# opencanusb2.net
KiCad netlist of a schematic drawn in EAGLE
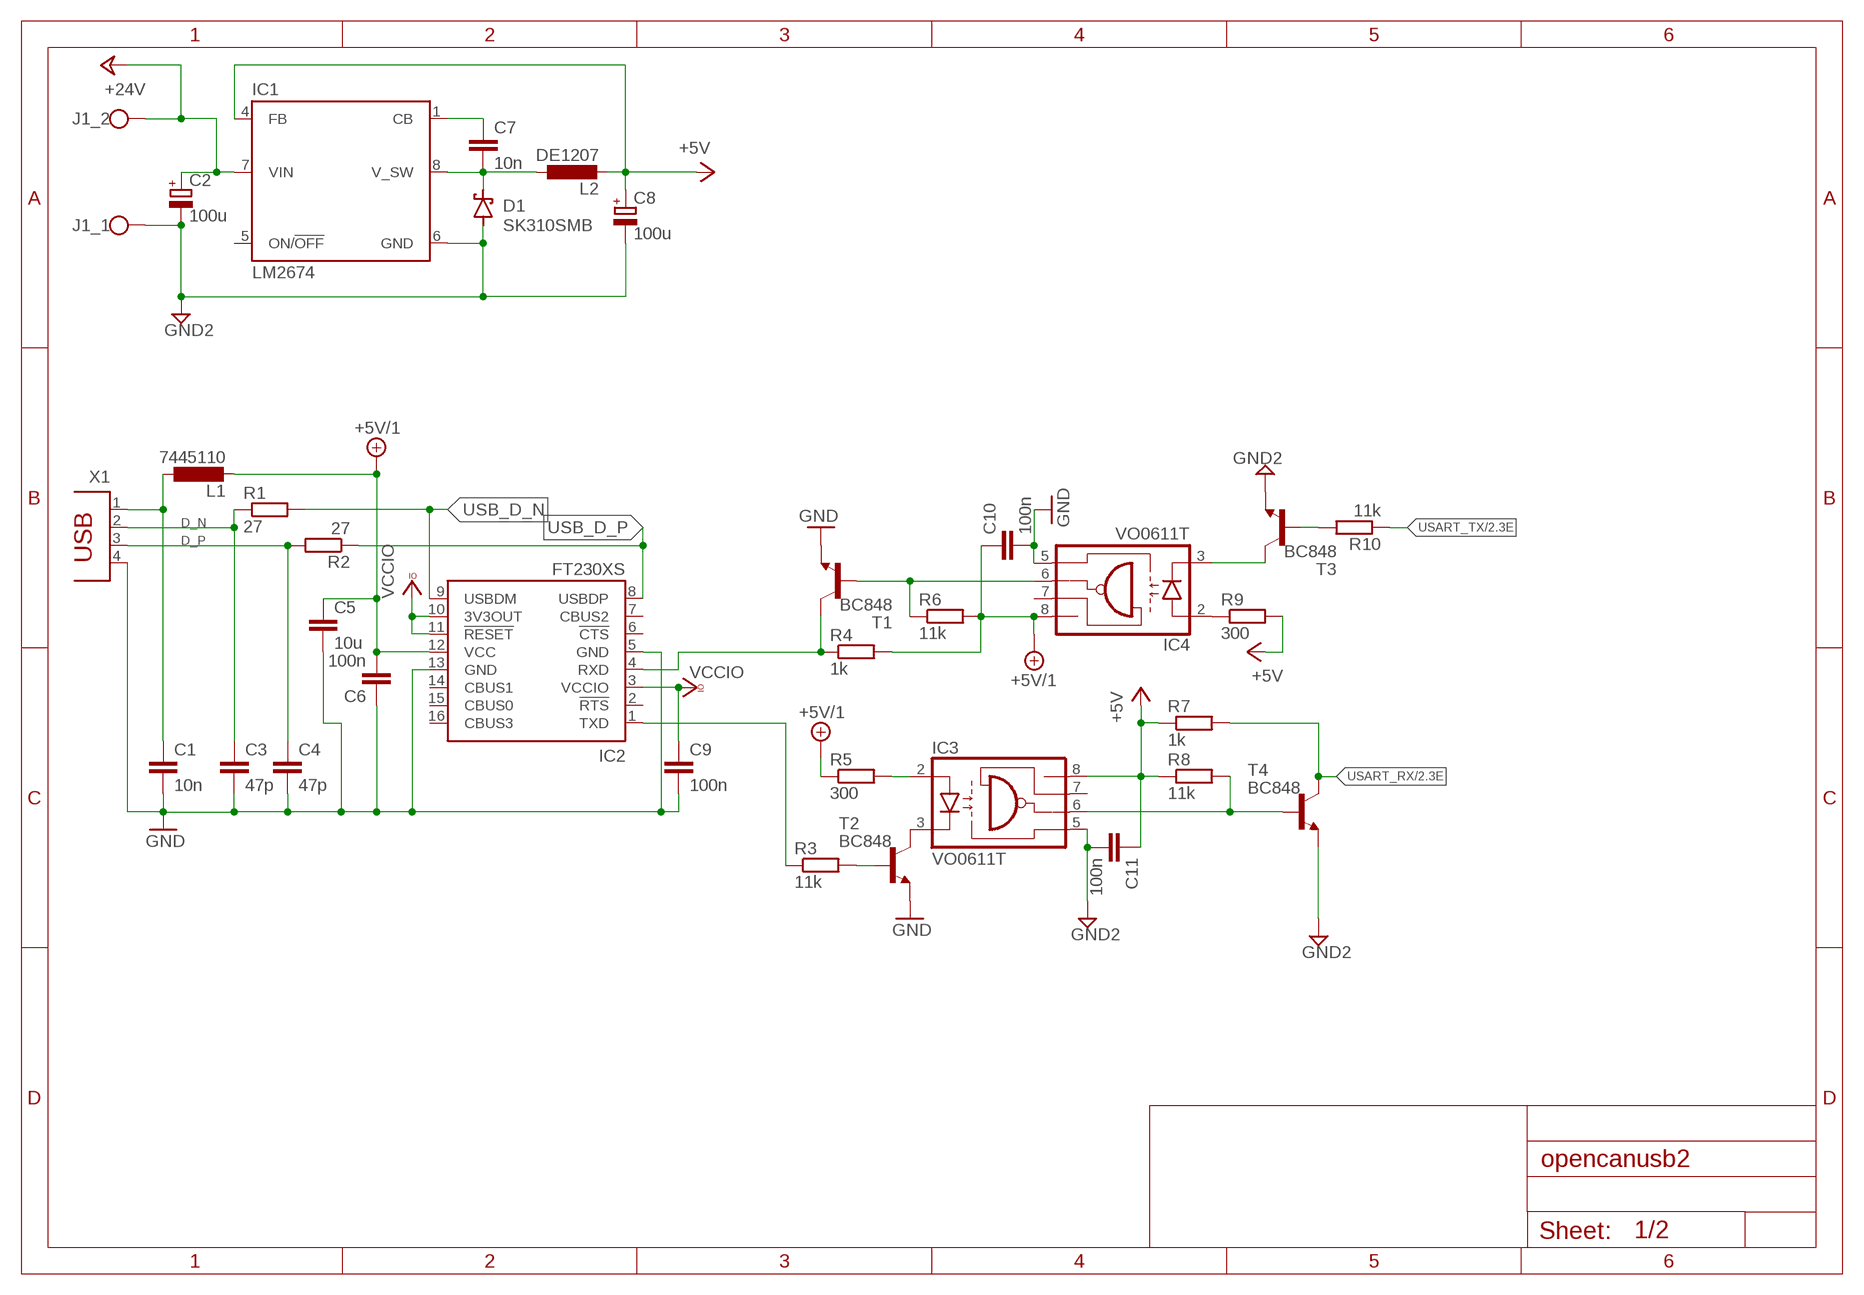
[diagram p0: schematic, sheet 1]
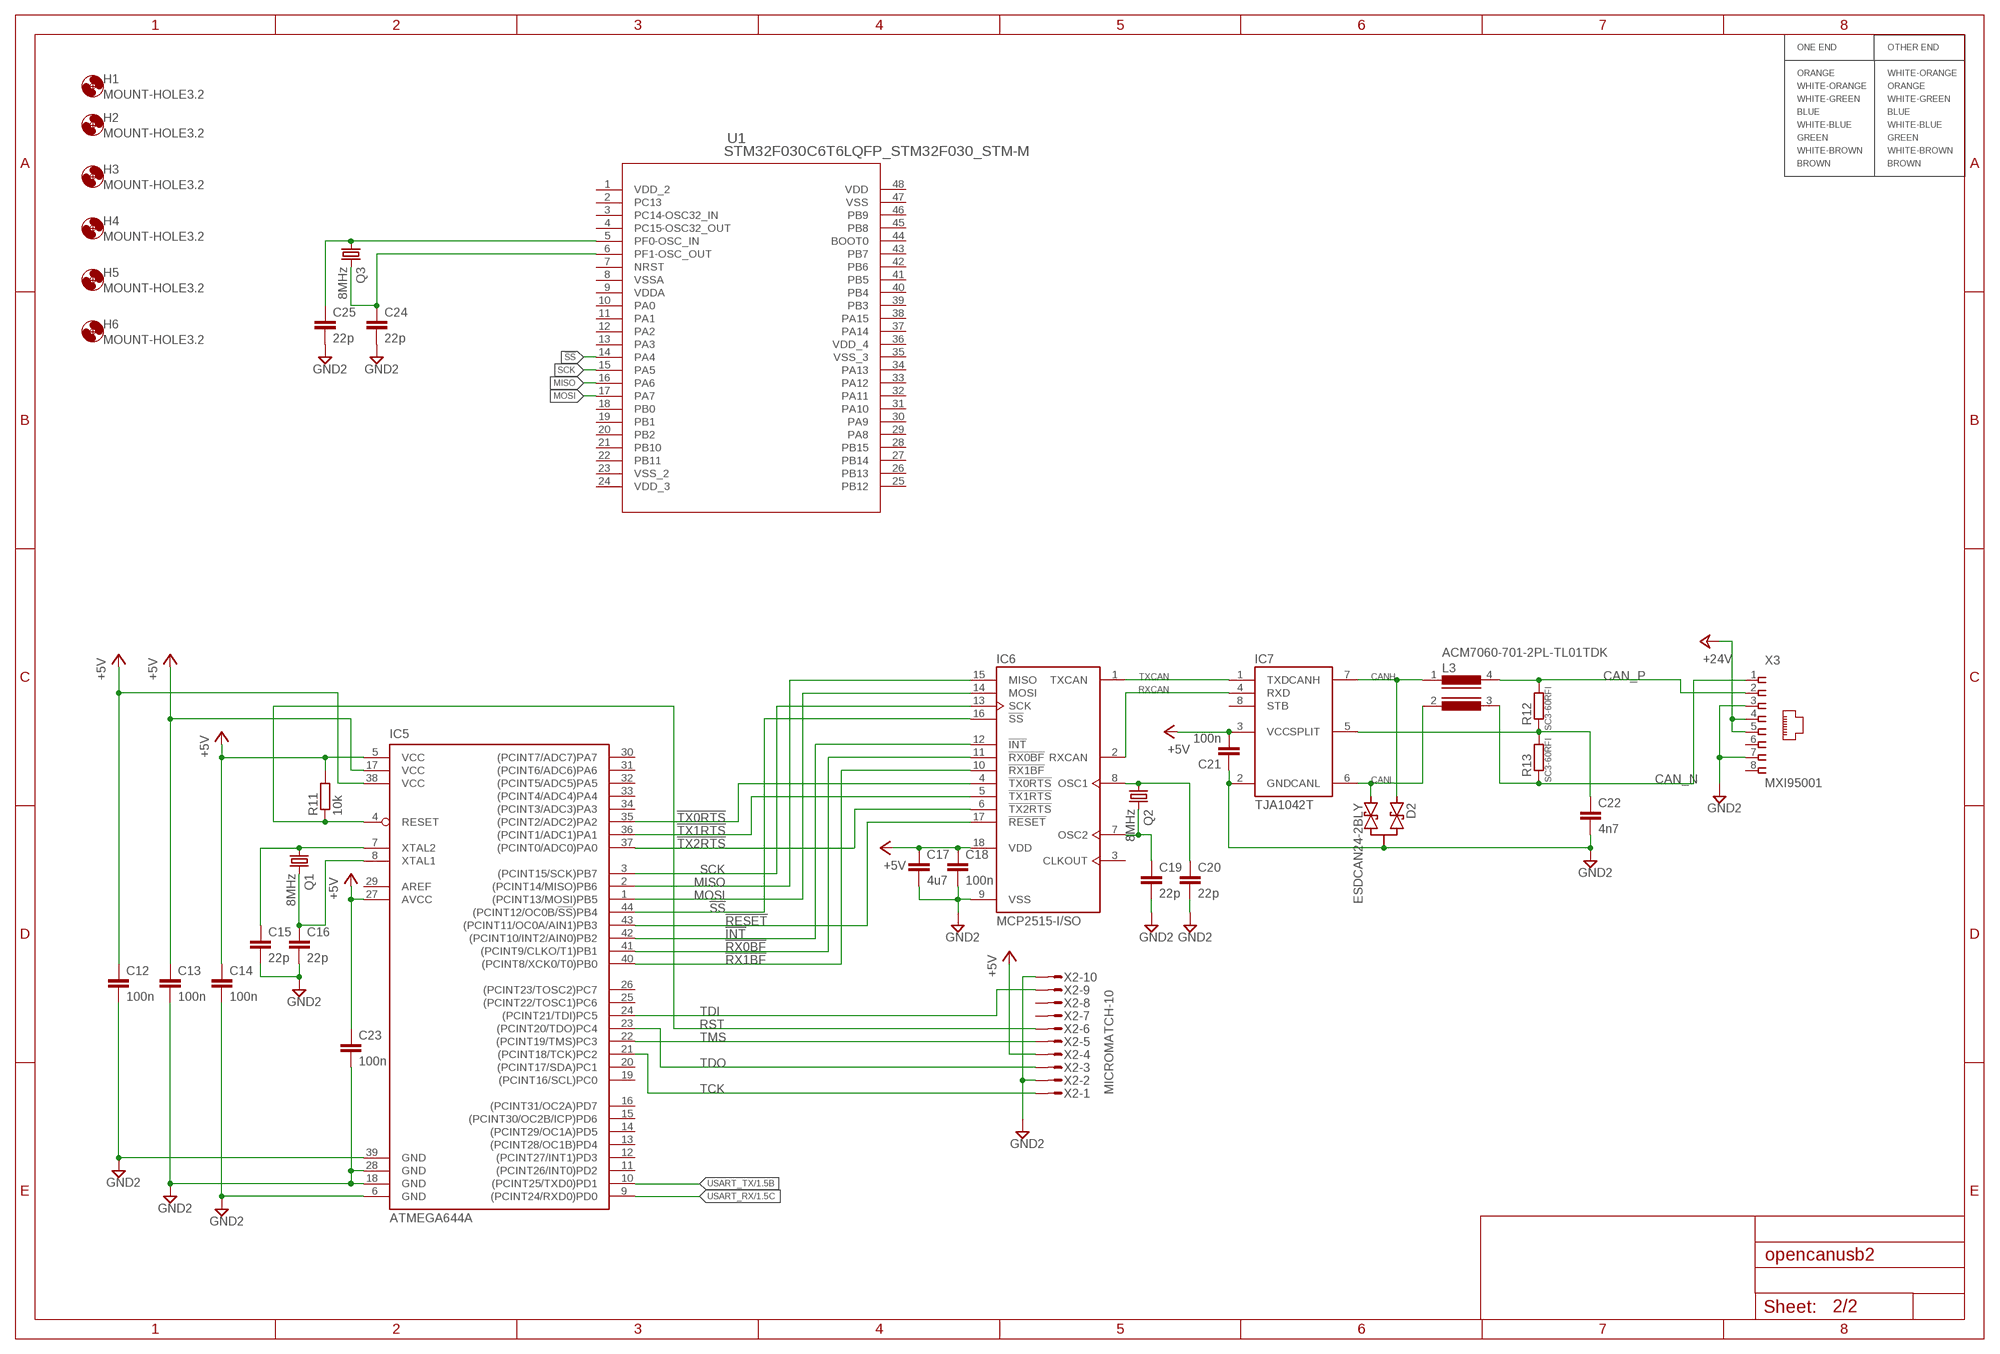
[diagram p1: schematic, sheet 2]

(export (version "E")
  (design (tool "Eeschema 10.0.6"))
  (components
    (comp (ref "C12")
      (value "100n")
      (footprint "eagle-import:C0805")
      (libsource (lib "eagle-import") (part "C-EUC0805"))
    )
    (comp (ref "C13")
      (value "100n")
      (footprint "eagle-import:C0805")
      (libsource (lib "eagle-import") (part "C-EUC0805"))
    )
    (comp (ref "C14")
      (value "100n")
      (footprint "eagle-import:C0805")
      (libsource (lib "eagle-import") (part "C-EUC0805"))
    )
    (comp (ref "C15")
      (value "22p")
      (footprint "eagle-import:C0805")
      (libsource (lib "eagle-import") (part "C-EUC0805"))
    )
    (comp (ref "C16")
      (value "22p")
      (footprint "eagle-import:C0805")
      (libsource (lib "eagle-import") (part "C-EUC0805"))
    )
    (comp (ref "C17")
      (value "4u7")
      (footprint "eagle-import:C0805")
      (libsource (lib "eagle-import") (part "C-EUC0805"))
    )
    (comp (ref "C18")
      (value "100n")
      (footprint "eagle-import:C0805")
      (libsource (lib "eagle-import") (part "C-EUC0805"))
    )
    (comp (ref "C19")
      (value "22p")
      (footprint "eagle-import:C0805")
      (libsource (lib "eagle-import") (part "C-EUC0805"))
    )
    (comp (ref "C20")
      (value "22p")
      (footprint "eagle-import:C0805")
      (libsource (lib "eagle-import") (part "C-EUC0805"))
    )
    (comp (ref "C21")
      (value "100n")
      (footprint "eagle-import:C0805")
      (libsource (lib "eagle-import") (part "C-EUC0805"))
    )
    (comp (ref "C22")
      (value "4n7")
      (footprint "eagle-import:C0805")
      (libsource (lib "eagle-import") (part "C-EUC0805"))
    )
    (comp (ref "C23")
      (value "100n")
      (footprint "eagle-import:C0805")
      (libsource (lib "eagle-import") (part "C-EUC0805"))
    )
    (comp (ref "C24")
      (value "22p")
      (footprint "eagle-import:C0805")
      (libsource (lib "eagle-import") (part "C-EUC0805"))
    )
    (comp (ref "C25")
      (value "22p")
      (footprint "eagle-import:C0805")
      (libsource (lib "eagle-import") (part "C-EUC0805"))
    )
    (comp (ref "D2")
      (value "ESDCAN24-2BLY")
      (footprint "eagle-import:SOT95P255X140-3N")
      (libsource (lib "eagle-import") (part "ESDCAN24-2BLY"))
    )
    (comp (ref "H1")
      (value "MOUNT-HOLE3.2")
      (footprint "eagle-import:3,2")
      (libsource (lib "eagle-import") (part "MOUNT-HOLE3.2"))
    )
    (comp (ref "H2")
      (value "MOUNT-HOLE3.2")
      (footprint "eagle-import:3,2")
      (libsource (lib "eagle-import") (part "MOUNT-HOLE3.2"))
    )
    (comp (ref "H3")
      (value "MOUNT-HOLE3.2")
      (footprint "eagle-import:3,2")
      (libsource (lib "eagle-import") (part "MOUNT-HOLE3.2"))
    )
    (comp (ref "H4")
      (value "MOUNT-HOLE3.2")
      (footprint "eagle-import:3,2")
      (libsource (lib "eagle-import") (part "MOUNT-HOLE3.2"))
    )
    (comp (ref "H5")
      (value "MOUNT-HOLE3.2")
      (footprint "eagle-import:3,2")
      (libsource (lib "eagle-import") (part "MOUNT-HOLE3.2"))
    )
    (comp (ref "H6")
      (value "MOUNT-HOLE3.2")
      (footprint "eagle-import:3,2")
      (libsource (lib "eagle-import") (part "MOUNT-HOLE3.2"))
    )
    (comp (ref "IC5")
      (value "ATMEGA644A")
      (footprint "eagle-import:TQFP44")
      (fields (field (name "MPN") "ATMEGA644PV-10AU"))
      (libsource (lib "eagle-import") (part "ATMEGA644A"))
    )
    (comp (ref "IC6")
      (value "MCP2515-I/SO")
      (footprint "eagle-import:SOIC127P1030X265-18N")
      (libsource (lib "eagle-import") (part "MCP2515-I/SO"))
    )
    (comp (ref "IC7")
      (value "TJA1042T")
      (footprint "eagle-import:SOIC127P600X265-8N")
      (libsource (lib "eagle-import") (part "TJA1042T"))
    )
    (comp (ref "L3")
      (value "ACM7060-701-2PL-TL01TDK")
      (footprint "eagle-import:ACM7060-701-2PL-TL01TDK")
      (libsource (lib "eagle-import") (part "ACM7060-701-2PL-TL01TDK"))
    )
    (comp (ref "Q1")
      (value "8MHz")
      (footprint "eagle-import:HC49UP")
      (libsource (lib "eagle-import") (part "CRYSTALHC49UP"))
    )
    (comp (ref "Q2")
      (value "8MHz")
      (footprint "eagle-import:HC49UP")
      (libsource (lib "eagle-import") (part "CRYSTALHC49UP"))
    )
    (comp (ref "Q3")
      (value "8MHz")
      (footprint "eagle-import:HC49UP")
      (libsource (lib "eagle-import") (part "CRYSTALHC49UP"))
    )
    (comp (ref "R11")
      (value "10k")
      (footprint "eagle-import:R1206")
      (libsource (lib "eagle-import") (part "R-EU_R1206"))
    )
    (comp (ref "R12")
      (value "SC3-60RFI")
      (footprint "eagle-import:RESC3163X76N")
      (libsource (lib "eagle-import") (part "SC3-XXRFI"))
    )
    (comp (ref "R13")
      (value "SC3-60RFI")
      (footprint "eagle-import:RESC3163X76N")
      (libsource (lib "eagle-import") (part "SC3-XXRFI"))
    )
    (comp (ref "U1")
      (value "STM32F030C6T6LQFP_STM32F030_STM-M")
      (footprint "eagle-import:LQFP_STM32F030_STM-M")
      (fields
        (field (name "MANUFACTURER_PART_NUMBER") "STM32F030C6T6")
        (field (name "COPYRIGHT") "Copyright (C) 2018 Accelerated Designs. All rights reserved")
      )
      (libsource (lib "eagle-import") (part "STM32F030C6T6LQFP_STM32F030_STM-M"))
    )
    (comp (ref "X2")
      (value "MICROMATCH-10")
      (footprint "eagle-import:MICROMATCH-10")
      (fields (field (name "MF") "FARNELL") (field (name "MPN") "8-215464-0"))
      (libsource (lib "eagle-import") (part "MICROMATCH-10"))
    )
    (comp (ref "X3")
      (value "MXI95001")
      (footprint "eagle-import:MXI950001")
      (libsource (lib "eagle-import") (part "MXI95001"))
    )
    (comp (ref "C1")
      (value "10n")
      (footprint "eagle-import:C0402")
      (libsource (lib "eagle-import") (part "C-EUC0402"))
    )
    (comp (ref "C2")
      (value "100u")
      (footprint "eagle-import:E5-8,5")
      (libsource (lib "eagle-import") (part "CPOL-EUE5-8.5"))
    )
    (comp (ref "C3")
      (value "47p")
      (footprint "eagle-import:C0603")
      (libsource (lib "eagle-import") (part "C-EUC0603"))
    )
    (comp (ref "C4")
      (value "47p")
      (footprint "eagle-import:C0603")
      (libsource (lib "eagle-import") (part "C-EUC0603"))
    )
    (comp (ref "C5")
      (value "10u")
      (footprint "eagle-import:C1210K")
      (libsource (lib "eagle-import") (part "C-EUC1210K"))
    )
    (comp (ref "C6")
      (value "100n")
      (footprint "eagle-import:C0805")
      (libsource (lib "eagle-import") (part "C-EUC0805"))
    )
    (comp (ref "C7")
      (value "10n")
      (footprint "eagle-import:C0805")
      (libsource (lib "eagle-import") (part "C-EUC0805"))
    )
    (comp (ref "C8")
      (value "100u")
      (footprint "eagle-import:E5-8,5")
      (libsource (lib "eagle-import") (part "CPOL-EUE5-8.5"))
    )
    (comp (ref "C9")
      (value "100n")
      (footprint "eagle-import:C0805")
      (libsource (lib "eagle-import") (part "C-EUC0805"))
    )
    (comp (ref "C10")
      (value "100n")
      (footprint "eagle-import:C0805")
      (libsource (lib "eagle-import") (part "C-EUC0805"))
    )
    (comp (ref "C11")
      (value "100n")
      (footprint "eagle-import:C0805")
      (libsource (lib "eagle-import") (part "C-EUC0805"))
    )
    (comp (ref "D1")
      (value "SK310SMB")
      (footprint "eagle-import:SMB")
      (libsource (lib "eagle-import") (part "MBRS130LT3"))
    )
    (comp (ref "IC1")
      (value "LM2674")
      (footprint "eagle-import:SOIC127P599X265-8N")
      (libsource (lib "eagle-import") (part "LM2674"))
    )
    (comp (ref "IC2")
      (value "FT230XS")
      (footprint "eagle-import:SSOP16")
      (libsource (lib "eagle-import") (part "FT230XS"))
    )
    (comp (ref "IC3")
      (value "VO0611T")
      (footprint "eagle-import:SOIC127P610X323-8N")
      (libsource (lib "eagle-import") (part "VO0611T"))
    )
    (comp (ref "IC4")
      (value "VO0611T")
      (footprint "eagle-import:SOIC127P610X323-8N")
      (libsource (lib "eagle-import") (part "VO0611T"))
    )
    (comp (ref "J1")
      (value "DG300-7.5")
      (footprint "eagle-import:DG300-7.5")
      (libsource (lib "eagle-import") (part "DG300-7.5"))
    )
    (comp (ref "L1")
      (value "7445110")
      (footprint "eagle-import:7445110")
      (libsource (lib "eagle-import") (part "7445110"))
    )
    (comp (ref "L2")
      (value "DE1207")
      (footprint "eagle-import:INDC120120X800N")
      (libsource (lib "eagle-import") (part "DE1207"))
    )
    (comp (ref "R1")
      (value "27")
      (footprint "eagle-import:R0805")
      (libsource (lib "eagle-import") (part "R-EU_R0805"))
    )
    (comp (ref "R2")
      (value "27")
      (footprint "eagle-import:R0805")
      (libsource (lib "eagle-import") (part "R-EU_R0805"))
    )
    (comp (ref "R3")
      (value "11k")
      (footprint "eagle-import:R1206")
      (libsource (lib "eagle-import") (part "R-EU_R1206"))
    )
    (comp (ref "R4")
      (value "1k")
      (footprint "eagle-import:R0805")
      (libsource (lib "eagle-import") (part "R-EU_R0805"))
    )
    (comp (ref "R5")
      (value "300")
      (footprint "eagle-import:R0805")
      (libsource (lib "eagle-import") (part "R-EU_R0805"))
    )
    (comp (ref "R6")
      (value "11k")
      (footprint "eagle-import:R1206")
      (libsource (lib "eagle-import") (part "R-EU_R1206"))
    )
    (comp (ref "R7")
      (value "1k")
      (footprint "eagle-import:R0805")
      (libsource (lib "eagle-import") (part "R-EU_R0805"))
    )
    (comp (ref "R8")
      (value "11k")
      (footprint "eagle-import:R1206")
      (libsource (lib "eagle-import") (part "R-EU_R1206"))
    )
    (comp (ref "R9")
      (value "300")
      (footprint "eagle-import:R0805")
      (libsource (lib "eagle-import") (part "R-EU_R0805"))
    )
    (comp (ref "R10")
      (value "11k")
      (footprint "eagle-import:R1206")
      (libsource (lib "eagle-import") (part "R-EU_R1206"))
    )
    (comp (ref "T1")
      (value "BC848")
      (footprint "eagle-import:SOT23")
      (libsource (lib "eagle-import") (part "BC848"))
    )
    (comp (ref "T2")
      (value "BC848")
      (footprint "eagle-import:SOT23")
      (libsource (lib "eagle-import") (part "BC848"))
    )
    (comp (ref "T3")
      (value "BC848")
      (footprint "eagle-import:SOT23")
      (libsource (lib "eagle-import") (part "BC848"))
    )
    (comp (ref "T4")
      (value "BC848")
      (footprint "eagle-import:SOT23")
      (libsource (lib "eagle-import") (part "BC848"))
    )
    (comp (ref "X1")
      (value "PN61729")
      (footprint "eagle-import:PN61729")
      (libsource (lib "eagle-import") (part "PN61729"))
    )
  )
  (nets
    (net (code "1") (name "+5V") (class "Default")
      (node (ref "C11") (pin "1") (pinfunction "1_1") (pintype "passive"))
      (node (ref "C12") (pin "1") (pinfunction "1_1") (pintype "passive"))
      (node (ref "C13") (pin "1") (pinfunction "1_1") (pintype "passive"))
      (node (ref "C14") (pin "1") (pinfunction "1_1") (pintype "passive"))
      (node (ref "C17") (pin "1") (pinfunction "1_1") (pintype "passive"))
      (node (ref "C18") (pin "1") (pinfunction "1_1") (pintype "passive"))
      (node (ref "C21") (pin "2") (pinfunction "2_2") (pintype "passive"))
      (node (ref "C23") (pin "1") (pinfunction "1_1") (pintype "passive"))
      (node (ref "C8") (pin "+") (pinfunction "+_+") (pintype "passive"))
      (node (ref "IC1") (pin "4") (pinfunction "FB_4") (pintype "power_in"))
      (node (ref "IC3") (pin "8") (pinfunction "VCC_8") (pintype "passive"))
      (node (ref "IC5") (pin "17") (pinfunction "VCC_17") (pintype "power_in"))
      (node (ref "IC5") (pin "27") (pinfunction "AVCC_27") (pintype "power_in"))
      (node (ref "IC5") (pin "38") (pinfunction "VCC_38") (pintype "power_in"))
      (node (ref "IC5") (pin "5") (pinfunction "VCC_5") (pintype "power_in"))
      (node (ref "IC6") (pin "18") (pinfunction "VDD_18") (pintype "power_in"))
      (node (ref "IC7") (pin "3") (pinfunction "VCC_3") (pintype "power_in"))
      (node (ref "L2") (pin "2") (pinfunction "2_2") (pintype "passive"))
      (node (ref "R11") (pin "2") (pinfunction "2_2") (pintype "passive"))
      (node (ref "R7") (pin "1") (pinfunction "1_1") (pintype "passive"))
      (node (ref "R8") (pin "1") (pinfunction "1_1") (pintype "passive"))
      (node (ref "R9") (pin "2") (pinfunction "2_2") (pintype "passive"))
      (node (ref "X2") (pin "4") (pinfunction "S_4") (pintype "passive"))
    )
    (net (code "2") (name "+5V{slash}1") (class "Default")
      (node (ref "C10") (pin "1") (pinfunction "1_1") (pintype "passive"))
      (node (ref "C5") (pin "1") (pinfunction "1_1") (pintype "passive"))
      (node (ref "C6") (pin "2") (pinfunction "2_2") (pintype "passive"))
      (node (ref "IC2") (pin "12") (pinfunction "VCC_12") (pintype "power_in"))
      (node (ref "IC4") (pin "8") (pinfunction "VCC_8") (pintype "passive"))
      (node (ref "L1") (pin "2") (pinfunction "2_2") (pintype "passive"))
      (node (ref "R4") (pin "2") (pinfunction "2_2") (pintype "passive"))
      (node (ref "R5") (pin "1") (pinfunction "1_1") (pintype "passive"))
      (node (ref "R6") (pin "2") (pinfunction "2_2") (pintype "passive"))
    )
    (net (code "3") (name "+24V") (class "Default")
      (node (ref "C2") (pin "+") (pinfunction "+_+") (pintype "passive"))
      (node (ref "IC1") (pin "7") (pinfunction "VIN_7") (pintype "power_in"))
      (node (ref "J1") (pin "P$2") (pinfunction "KL_P$2") (pintype "passive"))
      (node (ref "X3") (pin "4") (pinfunction "4_4") (pintype "passive"))
      (node (ref "X3") (pin "5") (pinfunction "5_5") (pintype "passive"))
    )
    (net (code "4") (name "CANH") (class "Default")
      (node (ref "D2") (pin "1") (pinfunction "1_1") (pintype "passive"))
      (node (ref "IC7") (pin "7") (pinfunction "CANH_7") (pintype "bidirectional"))
      (node (ref "L3") (pin "1") (pinfunction "1_1") (pintype "passive"))
    )
    (net (code "5") (name "CANL") (class "Default")
      (node (ref "D2") (pin "2") (pinfunction "2_2") (pintype "passive"))
      (node (ref "IC7") (pin "6") (pinfunction "CANL_6") (pintype "bidirectional"))
      (node (ref "L3") (pin "2") (pinfunction "2_2") (pintype "passive"))
    )
    (net (code "6") (name "CAN_N") (class "Default")
      (node (ref "L3") (pin "3") (pinfunction "3_3") (pintype "passive"))
      (node (ref "R13") (pin "1") (pinfunction "1_1") (pintype "passive"))
      (node (ref "X3") (pin "1") (pinfunction "1_1") (pintype "passive"))
    )
    (net (code "7") (name "CAN_P") (class "Default")
      (node (ref "L3") (pin "4") (pinfunction "4_4") (pintype "passive"))
      (node (ref "R12") (pin "2") (pinfunction "2_2") (pintype "passive"))
      (node (ref "X3") (pin "2") (pinfunction "2_2") (pintype "passive"))
    )
    (net (code "8") (name "D_N") (class "Default")
      (node (ref "C3") (pin "1") (pinfunction "1_1") (pintype "passive"))
      (node (ref "R1") (pin "1") (pinfunction "1_1") (pintype "passive"))
      (node (ref "X1") (pin "2") (pinfunction "2_2") (pintype "passive"))
    )
    (net (code "9") (name "D_P") (class "Default")
      (node (ref "C4") (pin "1") (pinfunction "1_1") (pintype "passive"))
      (node (ref "R2") (pin "2") (pinfunction "2_2") (pintype "passive"))
      (node (ref "X1") (pin "3") (pinfunction "3_3") (pintype "passive"))
    )
    (net (code "10") (name "GND") (class "Default")
      (node (ref "C1") (pin "2") (pinfunction "2_2") (pintype "passive"))
      (node (ref "C10") (pin "2") (pinfunction "2_2") (pintype "passive"))
      (node (ref "C3") (pin "2") (pinfunction "2_2") (pintype "passive"))
      (node (ref "C4") (pin "2") (pinfunction "2_2") (pintype "passive"))
      (node (ref "C5") (pin "2") (pinfunction "2_2") (pintype "passive"))
      (node (ref "C6") (pin "1") (pinfunction "1_1") (pintype "passive"))
      (node (ref "C9") (pin "2") (pinfunction "2_2") (pintype "passive"))
      (node (ref "IC2") (pin "13") (pinfunction "GND_13") (pintype "power_in"))
      (node (ref "IC2") (pin "5") (pinfunction "GND_5") (pintype "power_in"))
      (node (ref "IC4") (pin "5") (pinfunction "GND_5") (pintype "passive"))
      (node (ref "T1") (pin "2") (pinfunction "E_2") (pintype "passive"))
      (node (ref "T2") (pin "2") (pinfunction "E_2") (pintype "passive"))
      (node (ref "X1") (pin "4") (pinfunction "4_4") (pintype "passive"))
    )
    (net (code "11") (name "GND2") (class "Default")
      (node (ref "C11") (pin "2") (pinfunction "2_2") (pintype "passive"))
      (node (ref "C12") (pin "2") (pinfunction "2_2") (pintype "passive"))
      (node (ref "C13") (pin "2") (pinfunction "2_2") (pintype "passive"))
      (node (ref "C14") (pin "2") (pinfunction "2_2") (pintype "passive"))
      (node (ref "C15") (pin "2") (pinfunction "2_2") (pintype "passive"))
      (node (ref "C16") (pin "2") (pinfunction "2_2") (pintype "passive"))
      (node (ref "C17") (pin "2") (pinfunction "2_2") (pintype "passive"))
      (node (ref "C18") (pin "2") (pinfunction "2_2") (pintype "passive"))
      (node (ref "C19") (pin "2") (pinfunction "2_2") (pintype "passive"))
      (node (ref "C2") (pin "-") (pinfunction "-_-") (pintype "passive"))
      (node (ref "C20") (pin "2") (pinfunction "2_2") (pintype "passive"))
      (node (ref "C21") (pin "1") (pinfunction "1_1") (pintype "passive"))
      (node (ref "C22") (pin "2") (pinfunction "2_2") (pintype "passive"))
      (node (ref "C23") (pin "2") (pinfunction "2_2") (pintype "passive"))
      (node (ref "C24") (pin "2") (pinfunction "2_2") (pintype "passive"))
      (node (ref "C25") (pin "2") (pinfunction "2_2") (pintype "passive"))
      (node (ref "C8") (pin "-") (pinfunction "-_-") (pintype "passive"))
      (node (ref "D1") (pin "A") (pinfunction "A_A") (pintype "passive"))
      (node (ref "D2") (pin "3") (pinfunction "3_3") (pintype "passive"))
      (node (ref "IC1") (pin "6") (pinfunction "GND_6") (pintype "power_in"))
      (node (ref "IC3") (pin "5") (pinfunction "GND_5") (pintype "passive"))
      (node (ref "IC5") (pin "18") (pinfunction "GND_18") (pintype "power_in"))
      (node (ref "IC5") (pin "28") (pinfunction "GND_28") (pintype "power_in"))
      (node (ref "IC5") (pin "39") (pinfunction "GND_39") (pintype "power_in"))
      (node (ref "IC5") (pin "6") (pinfunction "GND_6") (pintype "power_in"))
      (node (ref "IC6") (pin "9") (pinfunction "VSS_9") (pintype "power_in"))
      (node (ref "IC7") (pin "2") (pinfunction "GND_2") (pintype "power_in"))
      (node (ref "J1") (pin "P$1") (pinfunction "KL_P$1") (pintype "passive"))
      (node (ref "T3") (pin "2") (pinfunction "E_2") (pintype "passive"))
      (node (ref "T4") (pin "2") (pinfunction "E_2") (pintype "passive"))
      (node (ref "X2") (pin "10") (pinfunction "S_10") (pintype "passive"))
      (node (ref "X2") (pin "2") (pinfunction "S_2") (pintype "passive"))
      (node (ref "X3") (pin "3") (pinfunction "3_3") (pintype "passive"))
      (node (ref "X3") (pin "7") (pinfunction "7_7") (pintype "passive"))
    )
    (net (code "12") (name "MISO") (class "Default")
      (node (ref "IC5") (pin "2") (pinfunction "(PCINT14/MISO)PB6_2") (pintype "bidirectional"))
      (node (ref "IC6") (pin "15") (pinfunction "MISO_15") (pintype "output"))
      (node (ref "U1") (pin "16") (pinfunction "PA6_16") (pintype "bidirectional"))
    )
    (net (code "13") (name "MOSI") (class "Default")
      (node (ref "IC5") (pin "1") (pinfunction "(PCINT13/MOSI)PB5_1") (pintype "bidirectional"))
      (node (ref "IC6") (pin "14") (pinfunction "MOSI_14") (pintype "input"))
      (node (ref "U1") (pin "17") (pinfunction "PA7_17") (pintype "bidirectional"))
    )
    (net (code "14") (name "Net-(C1-Pad1)") (class "Default")
      (node (ref "C1") (pin "1") (pinfunction "1_1") (pintype "passive"))
      (node (ref "L1") (pin "1") (pinfunction "1_1") (pintype "passive"))
      (node (ref "X1") (pin "1") (pinfunction "1_1") (pintype "passive"))
    )
    (net (code "15") (name "Net-(IC1-CB)") (class "Default")
      (node (ref "C7") (pin "1") (pinfunction "1_1") (pintype "passive"))
      (node (ref "IC1") (pin "1") (pinfunction "CB_1") (pintype "passive"))
    )
    (net (code "16") (name "Net-(IC1-V_SW)") (class "Default")
      (node (ref "C7") (pin "2") (pinfunction "2_2") (pintype "passive"))
      (node (ref "D1") (pin "C") (pinfunction "C_C") (pintype "passive"))
      (node (ref "IC1") (pin "8") (pinfunction "V_SW_8") (pintype "passive"))
      (node (ref "L2") (pin "1") (pinfunction "1_1") (pintype "passive"))
    )
    (net (code "17") (name "Net-(IC2-RXD)") (class "Default")
      (node (ref "IC2") (pin "4") (pinfunction "RXD_4") (pintype "input"))
      (node (ref "R4") (pin "1") (pinfunction "1_1") (pintype "passive"))
      (node (ref "T1") (pin "3") (pinfunction "C_3") (pintype "passive"))
    )
    (net (code "18") (name "Net-(IC2-TXD)") (class "Default")
      (node (ref "IC2") (pin "1") (pinfunction "TXD_1") (pintype "output"))
      (node (ref "R3") (pin "1") (pinfunction "1_1") (pintype "passive"))
    )
    (net (code "19") (name "Net-(IC3-A)") (class "Default")
      (node (ref "IC3") (pin "2") (pinfunction "A_2") (pintype "passive"))
      (node (ref "R5") (pin "2") (pinfunction "2_2") (pintype "passive"))
    )
    (net (code "20") (name "Net-(IC3-C)") (class "Default")
      (node (ref "IC3") (pin "3") (pinfunction "C_3") (pintype "passive"))
      (node (ref "T2") (pin "3") (pinfunction "C_3") (pintype "passive"))
    )
    (net (code "21") (name "Net-(IC3-VO)") (class "Default")
      (node (ref "IC3") (pin "6") (pinfunction "VO_6") (pintype "passive"))
      (node (ref "R8") (pin "2") (pinfunction "2_2") (pintype "passive"))
      (node (ref "T4") (pin "1") (pinfunction "B_1") (pintype "passive"))
    )
    (net (code "22") (name "Net-(IC4-A)") (class "Default")
      (node (ref "IC4") (pin "2") (pinfunction "A_2") (pintype "passive"))
      (node (ref "R9") (pin "1") (pinfunction "1_1") (pintype "passive"))
    )
    (net (code "23") (name "Net-(IC4-C)") (class "Default")
      (node (ref "IC4") (pin "3") (pinfunction "C_3") (pintype "passive"))
      (node (ref "T3") (pin "3") (pinfunction "C_3") (pintype "passive"))
    )
    (net (code "24") (name "Net-(IC4-VO)") (class "Default")
      (node (ref "IC4") (pin "6") (pinfunction "VO_6") (pintype "passive"))
      (node (ref "R6") (pin "1") (pinfunction "1_1") (pintype "passive"))
      (node (ref "T1") (pin "1") (pinfunction "B_1") (pintype "passive"))
    )
    (net (code "25") (name "Net-(IC5-XTAL1)") (class "Default")
      (node (ref "C16") (pin "1") (pinfunction "1_1") (pintype "passive"))
      (node (ref "IC5") (pin "8") (pinfunction "XTAL1_8") (pintype "bidirectional"))
      (node (ref "Q1") (pin "2") (pinfunction "2_2") (pintype "passive"))
    )
    (net (code "26") (name "Net-(IC5-XTAL2)") (class "Default")
      (node (ref "C15") (pin "1") (pinfunction "1_1") (pintype "passive"))
      (node (ref "IC5") (pin "7") (pinfunction "XTAL2_7") (pintype "bidirectional"))
      (node (ref "Q1") (pin "1") (pinfunction "1_1") (pintype "passive"))
    )
    (net (code "27") (name "Net-(IC6-OSC1)") (class "Default")
      (node (ref "C20") (pin "1") (pinfunction "1_1") (pintype "passive"))
      (node (ref "IC6") (pin "8") (pinfunction "OSC1_8") (pintype "input"))
      (node (ref "Q2") (pin "1") (pinfunction "1_1") (pintype "passive"))
    )
    (net (code "28") (name "Net-(IC6-OSC2)") (class "Default")
      (node (ref "C19") (pin "1") (pinfunction "1_1") (pintype "passive"))
      (node (ref "IC6") (pin "7") (pinfunction "OSC2_7") (pintype "output"))
      (node (ref "Q2") (pin "2") (pinfunction "2_2") (pintype "passive"))
    )
    (net (code "29") (name "Net-(IC7-SPLIT)") (class "Default")
      (node (ref "C22") (pin "1") (pinfunction "1_1") (pintype "passive"))
      (node (ref "IC7") (pin "5") (pinfunction "SPLIT_5") (pintype "bidirectional"))
      (node (ref "R12") (pin "1") (pinfunction "1_1") (pintype "passive"))
      (node (ref "R13") (pin "2") (pinfunction "2_2") (pintype "passive"))
    )
    (net (code "30") (name "Net-(T2-B)") (class "Default")
      (node (ref "R3") (pin "2") (pinfunction "2_2") (pintype "passive"))
      (node (ref "T2") (pin "1") (pinfunction "B_1") (pintype "passive"))
    )
    (net (code "31") (name "Net-(T3-B)") (class "Default")
      (node (ref "R10") (pin "2") (pinfunction "2_2") (pintype "passive"))
      (node (ref "T3") (pin "1") (pinfunction "B_1") (pintype "passive"))
    )
    (net (code "32") (name "Net-(U1-PF0-OSC_IN)") (class "Default")
      (node (ref "C25") (pin "1") (pinfunction "1_1") (pintype "passive"))
      (node (ref "Q3") (pin "1") (pinfunction "1_1") (pintype "passive"))
      (node (ref "U1") (pin "5") (pinfunction "PF0-OSC_IN_5") (pintype "bidirectional"))
    )
    (net (code "33") (name "Net-(U1-PF1-OSC_OUT)") (class "Default")
      (node (ref "C24") (pin "1") (pinfunction "1_1") (pintype "passive"))
      (node (ref "Q3") (pin "2") (pinfunction "2_2") (pintype "passive"))
      (node (ref "U1") (pin "6") (pinfunction "PF1-OSC_OUT_6") (pintype "output"))
    )
    (net (code "34") (name "ON{slash}~{OFF}") (class "Default")
      (node (ref "IC1") (pin "5") (pinfunction "ON/~{OFF}_5") (pintype "power_in"))
    )
    (net (code "35") (name "RST") (class "Default")
      (node (ref "IC5") (pin "4") (pinfunction "RESET_4") (pintype "input"))
      (node (ref "R11") (pin "1") (pinfunction "1_1") (pintype "passive"))
      (node (ref "X2") (pin "6") (pinfunction "S_6") (pintype "passive"))
    )
    (net (code "36") (name "RXCAN") (class "Default")
      (node (ref "IC6") (pin "2") (pinfunction "RXCAN_2") (pintype "bidirectional"))
      (node (ref "IC7") (pin "4") (pinfunction "RXD_4") (pintype "bidirectional"))
    )
    (net (code "37") (name "SCK") (class "Default")
      (node (ref "IC5") (pin "3") (pinfunction "(PCINT15/SCK)PB7_3") (pintype "bidirectional"))
      (node (ref "IC6") (pin "13") (pinfunction "SCK_13") (pintype "input"))
      (node (ref "U1") (pin "15") (pinfunction "PA5_15") (pintype "bidirectional"))
    )
    (net (code "38") (name "TCK") (class "Default")
      (node (ref "IC5") (pin "21") (pinfunction "(PCINT18/TCK)PC2_21") (pintype "output"))
      (node (ref "X2") (pin "1") (pinfunction "S_1") (pintype "passive"))
    )
    (net (code "39") (name "TDI") (class "Default")
      (node (ref "IC5") (pin "24") (pinfunction "(PCINT21/TDI)PC5_24") (pintype "output"))
      (node (ref "X2") (pin "9") (pinfunction "S_9") (pintype "passive"))
    )
    (net (code "40") (name "TDO") (class "Default")
      (node (ref "IC5") (pin "23") (pinfunction "(PCINT20/TDO)PC4_23") (pintype "output"))
      (node (ref "X2") (pin "3") (pinfunction "S_3") (pintype "passive"))
    )
    (net (code "41") (name "TMS") (class "Default")
      (node (ref "IC5") (pin "22") (pinfunction "(PCINT19/TMS)PC3_22") (pintype "output"))
      (node (ref "X2") (pin "5") (pinfunction "S_5") (pintype "passive"))
    )
    (net (code "42") (name "TXCAN") (class "Default")
      (node (ref "IC6") (pin "1") (pinfunction "TXCAN_1") (pintype "bidirectional"))
      (node (ref "IC7") (pin "1") (pinfunction "TXD_1") (pintype "bidirectional"))
    )
    (net (code "43") (name "USART_RX") (class "Default")
      (node (ref "IC5") (pin "9") (pinfunction "(PCINT24/RXD0)PD0_9") (pintype "bidirectional"))
      (node (ref "R7") (pin "2") (pinfunction "2_2") (pintype "passive"))
      (node (ref "T4") (pin "3") (pinfunction "C_3") (pintype "passive"))
    )
    (net (code "44") (name "USART_TX") (class "Default")
      (node (ref "IC5") (pin "10") (pinfunction "(PCINT25/TXD0)PD1_10") (pintype "bidirectional"))
      (node (ref "R10") (pin "1") (pinfunction "1_1") (pintype "passive"))
    )
    (net (code "45") (name "USB_D_N") (class "Default")
      (node (ref "IC2") (pin "9") (pinfunction "USBDM_9") (pintype "input"))
      (node (ref "R1") (pin "2") (pinfunction "2_2") (pintype "passive"))
    )
    (net (code "46") (name "USB_D_P") (class "Default")
      (node (ref "IC2") (pin "8") (pinfunction "USBDP_8") (pintype "input"))
      (node (ref "R2") (pin "1") (pinfunction "1_1") (pintype "passive"))
    )
    (net (code "47") (name "VCCIO") (class "Default")
      (node (ref "C9") (pin "1") (pinfunction "1_1") (pintype "passive"))
      (node (ref "IC2") (pin "10") (pinfunction "3V3OUT_10") (pintype "output"))
      (node (ref "IC2") (pin "11") (pinfunction "~{RESET}_11") (pintype "input"))
      (node (ref "IC2") (pin "3") (pinfunction "VCCIO_3") (pintype "power_in"))
    )
    (net (code "48") (name "VDD") (class "Default")
      (node (ref "U1") (pin "48") (pinfunction "VDD_48") (pintype "power_in"))
    )
    (net (code "49") (name "VDDA") (class "Default")
      (node (ref "U1") (pin "9") (pinfunction "VDDA_9") (pintype "power_in"))
    )
    (net (code "50") (name "VDD_2") (class "Default")
      (node (ref "U1") (pin "1") (pinfunction "VDD_2_1") (pintype "power_in"))
    )
    (net (code "51") (name "VDD_3") (class "Default")
      (node (ref "U1") (pin "24") (pinfunction "VDD_3_24") (pintype "power_in"))
    )
    (net (code "52") (name "VDD_4") (class "Default")
      (node (ref "U1") (pin "36") (pinfunction "VDD_4_36") (pintype "power_in"))
    )
    (net (code "53") (name "unconnected-(IC2-CBUS0-Pad15)") (class "Default")
      (node (ref "IC2") (pin "15") (pinfunction "CBUS0_15") (pintype "bidirectional"))
    )
    (net (code "54") (name "unconnected-(IC2-CBUS1-Pad14)") (class "Default")
      (node (ref "IC2") (pin "14") (pinfunction "CBUS1_14") (pintype "bidirectional"))
    )
    (net (code "55") (name "unconnected-(IC2-CBUS2-Pad7)") (class "Default")
      (node (ref "IC2") (pin "7") (pinfunction "CBUS2_7") (pintype "bidirectional"))
    )
    (net (code "56") (name "unconnected-(IC2-CBUS3-Pad16)") (class "Default")
      (node (ref "IC2") (pin "16") (pinfunction "CBUS3_16") (pintype "bidirectional"))
    )
    (net (code "57") (name "unconnected-(IC2-~{CTS}-Pad6)") (class "Default")
      (node (ref "IC2") (pin "6") (pinfunction "~{CTS}_6") (pintype "input"))
    )
    (net (code "58") (name "unconnected-(IC2-~{RTS}-Pad2)") (class "Default")
      (node (ref "IC2") (pin "2") (pinfunction "~{RTS}_2") (pintype "output"))
    )
    (net (code "59") (name "unconnected-(IC3-VE-Pad7)") (class "Default")
      (node (ref "IC3") (pin "7") (pinfunction "VE_7") (pintype "passive"))
    )
    (net (code "60") (name "unconnected-(IC4-VE-Pad7)") (class "Default")
      (node (ref "IC4") (pin "7") (pinfunction "VE_7") (pintype "passive"))
    )
    (net (code "61") (name "unconnected-(IC5-(PCINT3{slash}ADC3)PA3-Pad34)") (class "Default")
      (node (ref "IC5") (pin "34") (pinfunction "(PCINT3/ADC3)PA3_34") (pintype "bidirectional"))
    )
    (net (code "62") (name "unconnected-(IC5-(PCINT4{slash}ADC4)PA4-Pad33)") (class "Default")
      (node (ref "IC5") (pin "33") (pinfunction "(PCINT4/ADC4)PA4_33") (pintype "bidirectional"))
    )
    (net (code "63") (name "unconnected-(IC5-(PCINT5{slash}ADC5)PA5-Pad32)") (class "Default")
      (node (ref "IC5") (pin "32") (pinfunction "(PCINT5/ADC5)PA5_32") (pintype "bidirectional"))
    )
    (net (code "64") (name "unconnected-(IC5-(PCINT6{slash}ADC6)PA6-Pad31)") (class "Default")
      (node (ref "IC5") (pin "31") (pinfunction "(PCINT6/ADC6)PA6_31") (pintype "bidirectional"))
    )
    (net (code "65") (name "unconnected-(IC5-(PCINT7{slash}ADC7)PA7-Pad30)") (class "Default")
      (node (ref "IC5") (pin "30") (pinfunction "(PCINT7/ADC7)PA7_30") (pintype "bidirectional"))
    )
    (net (code "66") (name "unconnected-(IC5-(PCINT16{slash}SCL)PC0-Pad19)") (class "Default")
      (node (ref "IC5") (pin "19") (pinfunction "(PCINT16/SCL)PC0_19") (pintype "output"))
    )
    (net (code "67") (name "unconnected-(IC5-(PCINT17{slash}SDA)PC1-Pad20)") (class "Default")
      (node (ref "IC5") (pin "20") (pinfunction "(PCINT17/SDA)PC1_20") (pintype "output"))
    )
    (net (code "68") (name "unconnected-(IC5-(PCINT22{slash}TOSC1)PC6-Pad25)") (class "Default")
      (node (ref "IC5") (pin "25") (pinfunction "(PCINT22/TOSC1)PC6_25") (pintype "output"))
    )
    (net (code "69") (name "unconnected-(IC5-(PCINT23{slash}TOSC2)PC7-Pad26)") (class "Default")
      (node (ref "IC5") (pin "26") (pinfunction "(PCINT23/TOSC2)PC7_26") (pintype "output"))
    )
    (net (code "70") (name "unconnected-(IC5-(PCINT26{slash}INT0)PD2-Pad11)") (class "Default")
      (node (ref "IC5") (pin "11") (pinfunction "(PCINT26/INT0)PD2_11") (pintype "bidirectional"))
    )
    (net (code "71") (name "unconnected-(IC5-(PCINT27{slash}INT1)PD3-Pad12)") (class "Default")
      (node (ref "IC5") (pin "12") (pinfunction "(PCINT27/INT1)PD3_12") (pintype "bidirectional"))
    )
    (net (code "72") (name "unconnected-(IC5-(PCINT28{slash}OC1B)PD4-Pad13)") (class "Default")
      (node (ref "IC5") (pin "13") (pinfunction "(PCINT28/OC1B)PD4_13") (pintype "bidirectional"))
    )
    (net (code "73") (name "unconnected-(IC5-(PCINT29{slash}OC1A)PD5-Pad14)") (class "Default")
      (node (ref "IC5") (pin "14") (pinfunction "(PCINT29/OC1A)PD5_14") (pintype "bidirectional"))
    )
    (net (code "74") (name "unconnected-(IC5-(PCINT30{slash}OC2B{slash}ICP)PD6-Pad15)") (class "Default")
      (node (ref "IC5") (pin "15") (pinfunction "(PCINT30/OC2B/ICP)PD6_15") (pintype "bidirectional"))
    )
    (net (code "75") (name "unconnected-(IC5-(PCINT31{slash}OC2A)PD7-Pad16)") (class "Default")
      (node (ref "IC5") (pin "16") (pinfunction "(PCINT31/OC2A)PD7_16") (pintype "bidirectional"))
    )
    (net (code "76") (name "unconnected-(IC5-AREF-Pad29)") (class "Default")
      (node (ref "IC5") (pin "29") (pinfunction "AREF_29") (pintype "passive"))
    )
    (net (code "77") (name "unconnected-(IC6-CLKOUT-Pad3)") (class "Default")
      (node (ref "IC6") (pin "3") (pinfunction "CLKOUT_3") (pintype "output"))
    )
    (net (code "78") (name "unconnected-(IC7-STB-Pad8)") (class "Default")
      (node (ref "IC7") (pin "8") (pinfunction "STB_8") (pintype "bidirectional"))
    )
    (net (code "79") (name "unconnected-(U1-BOOT0-Pad44)") (class "Default")
      (node (ref "U1") (pin "44") (pinfunction "BOOT0_44") (pintype "passive"))
    )
    (net (code "80") (name "unconnected-(U1-NRST-Pad7)") (class "Default")
      (node (ref "U1") (pin "7") (pinfunction "NRST_7") (pintype "passive"))
    )
    (net (code "81") (name "unconnected-(U1-PA0-Pad10)") (class "Default")
      (node (ref "U1") (pin "10") (pinfunction "PA0_10") (pintype "bidirectional"))
    )
    (net (code "82") (name "unconnected-(U1-PA1-Pad11)") (class "Default")
      (node (ref "U1") (pin "11") (pinfunction "PA1_11") (pintype "bidirectional"))
    )
    (net (code "83") (name "unconnected-(U1-PA2-Pad12)") (class "Default")
      (node (ref "U1") (pin "12") (pinfunction "PA2_12") (pintype "bidirectional"))
    )
    (net (code "84") (name "unconnected-(U1-PA3-Pad13)") (class "Default")
      (node (ref "U1") (pin "13") (pinfunction "PA3_13") (pintype "bidirectional"))
    )
    (net (code "85") (name "unconnected-(U1-PA8-Pad29)") (class "Default")
      (node (ref "U1") (pin "29") (pinfunction "PA8_29") (pintype "bidirectional"))
    )
    (net (code "86") (name "unconnected-(U1-PA9-Pad30)") (class "Default")
      (node (ref "U1") (pin "30") (pinfunction "PA9_30") (pintype "bidirectional"))
    )
    (net (code "87") (name "unconnected-(U1-PA10-Pad31)") (class "Default")
      (node (ref "U1") (pin "31") (pinfunction "PA10_31") (pintype "bidirectional"))
    )
    (net (code "88") (name "unconnected-(U1-PA11-Pad32)") (class "Default")
      (node (ref "U1") (pin "32") (pinfunction "PA11_32") (pintype "bidirectional"))
    )
    (net (code "89") (name "unconnected-(U1-PA12-Pad33)") (class "Default")
      (node (ref "U1") (pin "33") (pinfunction "PA12_33") (pintype "bidirectional"))
    )
    (net (code "90") (name "unconnected-(U1-PA13-Pad34)") (class "Default")
      (node (ref "U1") (pin "34") (pinfunction "PA13_34") (pintype "bidirectional"))
    )
    (net (code "91") (name "unconnected-(U1-PA14-Pad37)") (class "Default")
      (node (ref "U1") (pin "37") (pinfunction "PA14_37") (pintype "bidirectional"))
    )
    (net (code "92") (name "unconnected-(U1-PA15-Pad38)") (class "Default")
      (node (ref "U1") (pin "38") (pinfunction "PA15_38") (pintype "bidirectional"))
    )
    (net (code "93") (name "unconnected-(U1-PB0-Pad18)") (class "Default")
      (node (ref "U1") (pin "18") (pinfunction "PB0_18") (pintype "bidirectional"))
    )
    (net (code "94") (name "unconnected-(U1-PB1-Pad19)") (class "Default")
      (node (ref "U1") (pin "19") (pinfunction "PB1_19") (pintype "bidirectional"))
    )
    (net (code "95") (name "unconnected-(U1-PB2-Pad20)") (class "Default")
      (node (ref "U1") (pin "20") (pinfunction "PB2_20") (pintype "bidirectional"))
    )
    (net (code "96") (name "unconnected-(U1-PB3-Pad39)") (class "Default")
      (node (ref "U1") (pin "39") (pinfunction "PB3_39") (pintype "bidirectional"))
    )
    (net (code "97") (name "unconnected-(U1-PB4-Pad40)") (class "Default")
      (node (ref "U1") (pin "40") (pinfunction "PB4_40") (pintype "bidirectional"))
    )
    (net (code "98") (name "unconnected-(U1-PB5-Pad41)") (class "Default")
      (node (ref "U1") (pin "41") (pinfunction "PB5_41") (pintype "bidirectional"))
    )
    (net (code "99") (name "unconnected-(U1-PB6-Pad42)") (class "Default")
      (node (ref "U1") (pin "42") (pinfunction "PB6_42") (pintype "bidirectional"))
    )
    (net (code "100") (name "unconnected-(U1-PB7-Pad43)") (class "Default")
      (node (ref "U1") (pin "43") (pinfunction "PB7_43") (pintype "bidirectional"))
    )
    (net (code "101") (name "unconnected-(U1-PB8-Pad45)") (class "Default")
      (node (ref "U1") (pin "45") (pinfunction "PB8_45") (pintype "bidirectional"))
    )
    (net (code "102") (name "unconnected-(U1-PB9-Pad46)") (class "Default")
      (node (ref "U1") (pin "46") (pinfunction "PB9_46") (pintype "bidirectional"))
    )
    (net (code "103") (name "unconnected-(U1-PB10-Pad21)") (class "Default")
      (node (ref "U1") (pin "21") (pinfunction "PB10_21") (pintype "bidirectional"))
    )
    (net (code "104") (name "unconnected-(U1-PB11-Pad22)") (class "Default")
      (node (ref "U1") (pin "22") (pinfunction "PB11_22") (pintype "bidirectional"))
    )
    (net (code "105") (name "unconnected-(U1-PB12-Pad25)") (class "Default")
      (node (ref "U1") (pin "25") (pinfunction "PB12_25") (pintype "bidirectional"))
    )
    (net (code "106") (name "unconnected-(U1-PB13-Pad26)") (class "Default")
      (node (ref "U1") (pin "26") (pinfunction "PB13_26") (pintype "bidirectional"))
    )
    (net (code "107") (name "unconnected-(U1-PB14-Pad27)") (class "Default")
      (node (ref "U1") (pin "27") (pinfunction "PB14_27") (pintype "bidirectional"))
    )
    (net (code "108") (name "unconnected-(U1-PB15-Pad28)") (class "Default")
      (node (ref "U1") (pin "28") (pinfunction "PB15_28") (pintype "bidirectional"))
    )
    (net (code "109") (name "unconnected-(U1-PC13-Pad2)") (class "Default")
      (node (ref "U1") (pin "2") (pinfunction "PC13_2") (pintype "bidirectional"))
    )
    (net (code "110") (name "unconnected-(U1-PC14-OSC32_IN-Pad3)") (class "Default")
      (node (ref "U1") (pin "3") (pinfunction "PC14-OSC32_IN_3") (pintype "bidirectional"))
    )
    (net (code "111") (name "unconnected-(U1-PC15-OSC32_OUT-Pad4)") (class "Default")
      (node (ref "U1") (pin "4") (pinfunction "PC15-OSC32_OUT_4") (pintype "output"))
    )
    (net (code "112") (name "unconnected-(U1-VSS-Pad47)") (class "Default")
      (node (ref "U1") (pin "47") (pinfunction "VSS_47") (pintype "passive"))
    )
    (net (code "113") (name "unconnected-(U1-VSSA-Pad8)") (class "Default")
      (node (ref "U1") (pin "8") (pinfunction "VSSA_8") (pintype "passive"))
    )
    (net (code "114") (name "unconnected-(U1-VSS_2-Pad23)") (class "Default")
      (node (ref "U1") (pin "23") (pinfunction "VSS_2_23") (pintype "passive"))
    )
    (net (code "115") (name "unconnected-(U1-VSS_3-Pad35)") (class "Default")
      (node (ref "U1") (pin "35") (pinfunction "VSS_3_35") (pintype "passive"))
    )
    (net (code "116") (name "unconnected-(X2H-S-Pad7)") (class "Default")
      (node (ref "X2") (pin "7") (pinfunction "S_7") (pintype "passive"))
    )
    (net (code "117") (name "unconnected-(X2I-S-Pad8)") (class "Default")
      (node (ref "X2") (pin "8") (pinfunction "S_8") (pintype "passive"))
    )
    (net (code "118") (name "unconnected-(X3-Pad6)") (class "Default")
      (node (ref "X3") (pin "6") (pinfunction "6_6") (pintype "passive"))
    )
    (net (code "119") (name "unconnected-(X3-Pad8)") (class "Default")
      (node (ref "X3") (pin "8") (pinfunction "8_8") (pintype "passive"))
    )
    (net (code "120") (name "~{INT}") (class "Default")
      (node (ref "IC5") (pin "42") (pinfunction "(PCINT10/INT2/AIN0)PB2_42") (pintype "bidirectional"))
      (node (ref "IC6") (pin "12") (pinfunction "~{INT}_12") (pintype "output"))
    )
    (net (code "121") (name "~{RESET}") (class "Default")
      (node (ref "IC5") (pin "43") (pinfunction "(PCINT11/OC0A/AIN1)PB3_43") (pintype "bidirectional"))
      (node (ref "IC6") (pin "17") (pinfunction "~{RESET}_17") (pintype "input"))
    )
    (net (code "122") (name "~{RX0BF}") (class "Default")
      (node (ref "IC5") (pin "41") (pinfunction "(PCINT9/CLKO/T1)PB1_41") (pintype "bidirectional"))
      (node (ref "IC6") (pin "11") (pinfunction "~{RX0BF}_11") (pintype "output"))
    )
    (net (code "123") (name "~{RX1BF}") (class "Default")
      (node (ref "IC5") (pin "40") (pinfunction "(PCINT8/XCK0/T0)PB0_40") (pintype "bidirectional"))
      (node (ref "IC6") (pin "10") (pinfunction "~{RX1BF}_10") (pintype "output"))
    )
    (net (code "124") (name "~{SS}") (class "Default")
      (node (ref "IC5") (pin "44") (pinfunction "(PCINT12/OC0B/~{SS})PB4_44") (pintype "bidirectional"))
      (node (ref "IC6") (pin "16") (pinfunction "~{SS}_16") (pintype "input"))
      (node (ref "U1") (pin "14") (pinfunction "PA4_14") (pintype "bidirectional"))
    )
    (net (code "125") (name "~{TX0RTS}") (class "Default")
      (node (ref "IC5") (pin "35") (pinfunction "(PCINT2/ADC2)PA2_35") (pintype "bidirectional"))
      (node (ref "IC6") (pin "4") (pinfunction "~{TX0RTS}_4") (pintype "input"))
    )
    (net (code "126") (name "~{TX1RTS}") (class "Default")
      (node (ref "IC5") (pin "36") (pinfunction "(PCINT1/ADC1)PA1_36") (pintype "bidirectional"))
      (node (ref "IC6") (pin "5") (pinfunction "~{TX1RTS}_5") (pintype "input"))
    )
    (net (code "127") (name "~{TX2RTS}") (class "Default")
      (node (ref "IC5") (pin "37") (pinfunction "(PCINT0/ADC0)PA0_37") (pintype "bidirectional"))
      (node (ref "IC6") (pin "6") (pinfunction "~{TX2RTS}_6") (pintype "input"))
    )
  )
)
